# Validation.net
KiCad netlist of a schematic drawn in EAGLE
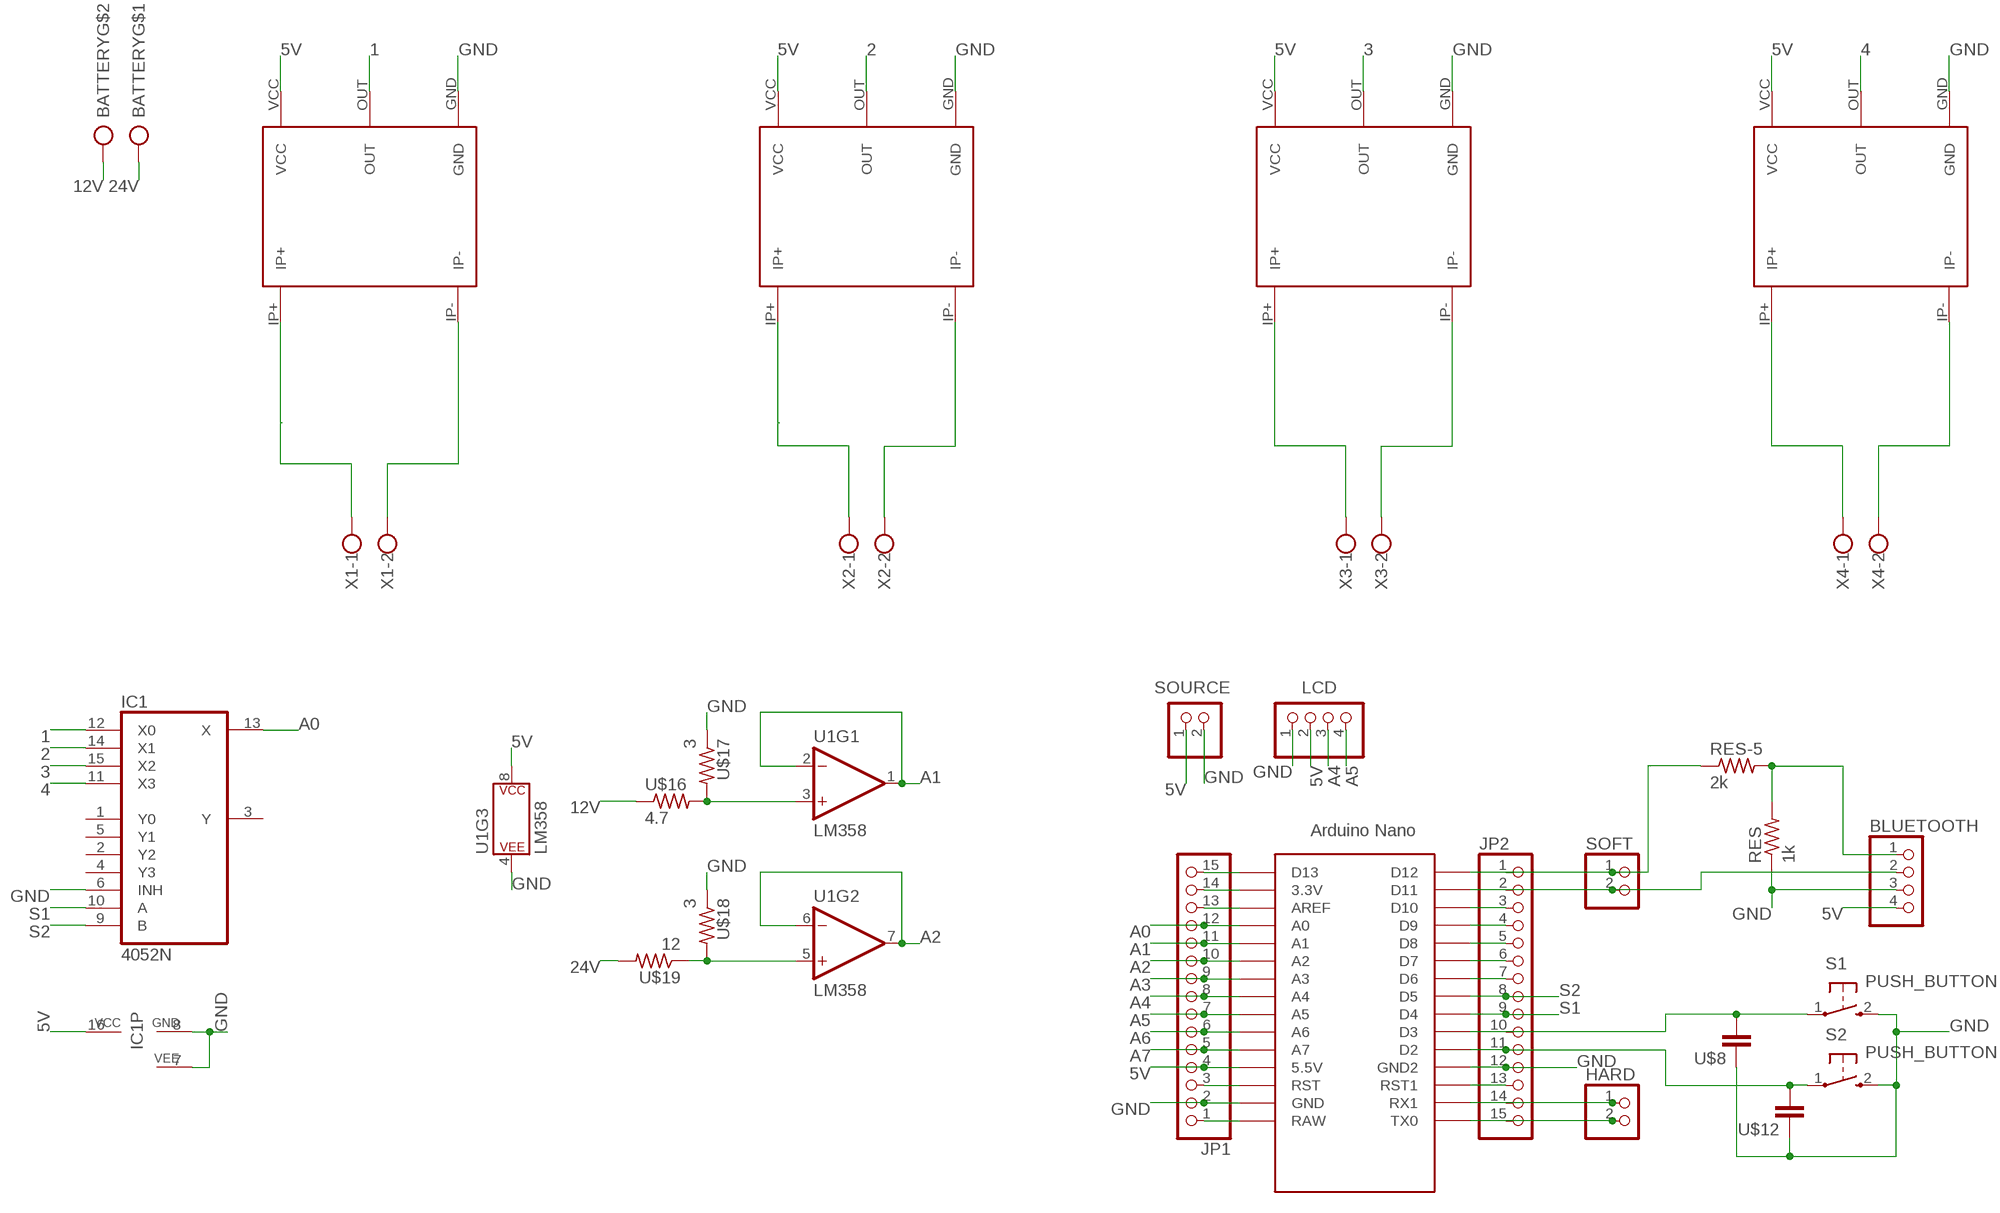
[diagram p0: schematic, sheet 1]

(export (version "E")
  (design (tool "Eeschema 10.0.6"))
  (components
    (comp (ref "BATTERY")
      (value "CON_PTR_2")
      (footprint "eagle-import:AK300_2")
      (libsource (lib "eagle-import") (part "CON_PTR_2"))
    )
    (comp (ref "BLUETOOTH")
      (value "PINHD-4_DATA")
      (footprint "eagle-import:1X04_DATA")
      (libsource (lib "eagle-import") (part "PINHD-4_DATA"))
    )
    (comp (ref "HARD")
      (value "PINHD-2_DATA")
      (footprint "eagle-import:1X02_DATA")
      (libsource (lib "eagle-import") (part "PINHD-2_DATA"))
    )
    (comp (ref "IC1")
      (value "4052N")
      (footprint "eagle-import:DIL16")
      (libsource (lib "eagle-import") (part "4052N"))
    )
    (comp (ref "JP1")
      (value "PINHD-1X15")
      (footprint "eagle-import:1X15")
      (libsource (lib "eagle-import") (part "PINHD-1X15"))
    )
    (comp (ref "JP2")
      (value "PINHD-1X15")
      (footprint "eagle-import:1X15")
      (libsource (lib "eagle-import") (part "PINHD-1X15"))
    )
    (comp (ref "LCD")
      (value "PINHD-4_DATA")
      (footprint "eagle-import:1X04_DATA")
      (libsource (lib "eagle-import") (part "PINHD-4_DATA"))
    )
    (comp (ref "RES")
      (value "1k")
      (footprint "eagle-import:0204_5")
      (libsource (lib "eagle-import") (part "RES-5"))
    )
    (comp (ref "RES-5")
      (value "2k")
      (footprint "eagle-import:0204_5")
      (libsource (lib "eagle-import") (part "RES-5"))
    )
    (comp (ref "S1")
      (value "PUSH_BUTTON")
      (footprint "eagle-import:B3F-10XX")
      (libsource (lib "eagle-import") (part "PUSH_BUTTON"))
    )
    (comp (ref "S2")
      (value "PUSH_BUTTON")
      (footprint "eagle-import:B3F-10XX")
      (libsource (lib "eagle-import") (part "PUSH_BUTTON"))
    )
    (comp (ref "SOFT")
      (value "PINHD-2_DATA")
      (footprint "eagle-import:1X02_DATA")
      (libsource (lib "eagle-import") (part "PINHD-2_DATA"))
    )
    (comp (ref "SOURCE")
      (value "PINHD-2_DATA")
      (footprint "eagle-import:1X02_DATA")
      (libsource (lib "eagle-import") (part "PINHD-2_DATA"))
    )
    (comp (ref "U$1")
      (value "ASC712_MODULE")
      (footprint "eagle-import:ASC712_MODULE")
      (libsource (lib "eagle-import") (part "ASC712_MODULE"))
    )
    (comp (ref "U$4")
      (value "ARDUINO_NANO")
      (footprint "eagle-import:NANO")
      (libsource (lib "eagle-import") (part "ARDUINO_NANO"))
    )
    (comp (ref "U$5")
      (value "ASC712_MODULE")
      (footprint "eagle-import:ASC712_MODULE")
      (libsource (lib "eagle-import") (part "ASC712_MODULE"))
    )
    (comp (ref "U$8")
      (value "CAPACITOR")
      (footprint "eagle-import:C025-025X050")
      (libsource (lib "eagle-import") (part "CAPACITOR"))
    )
    (comp (ref "U$9")
      (value "ASC712_MODULE")
      (footprint "eagle-import:ASC712_MODULE")
      (libsource (lib "eagle-import") (part "ASC712_MODULE"))
    )
    (comp (ref "U$12")
      (value "CAPACITOR")
      (footprint "eagle-import:C025-025X050")
      (libsource (lib "eagle-import") (part "CAPACITOR"))
    )
    (comp (ref "U$13")
      (value "ASC712_MODULE")
      (footprint "eagle-import:ASC712_MODULE")
      (libsource (lib "eagle-import") (part "ASC712_MODULE"))
    )
    (comp (ref "U$16")
      (value "4.7")
      (footprint "eagle-import:0204_7")
      (libsource (lib "eagle-import") (part "RES-7"))
    )
    (comp (ref "U$17")
      (value "3")
      (footprint "eagle-import:0204_7")
      (libsource (lib "eagle-import") (part "RES-7"))
    )
    (comp (ref "U$18")
      (value "3")
      (footprint "eagle-import:0204_7")
      (libsource (lib "eagle-import") (part "RES-7"))
    )
    (comp (ref "U$19")
      (value "12")
      (footprint "eagle-import:0204_7")
      (libsource (lib "eagle-import") (part "RES-7"))
    )
    (comp (ref "U1")
      (value "LM358")
      (footprint "eagle-import:DIP08")
      (libsource (lib "eagle-import") (part "LM358"))
    )
    (comp (ref "X1")
      (value "ROSTA.POWER")
      (footprint "eagle-import:W239-302")
      (libsource (lib "eagle-import") (part "ROSTA.POWER"))
    )
    (comp (ref "X2")
      (value "ROSTA.POWER")
      (footprint "eagle-import:W239-302")
      (libsource (lib "eagle-import") (part "ROSTA.POWER"))
    )
    (comp (ref "X3")
      (value "ROSTA.POWER")
      (footprint "eagle-import:W239-302")
      (libsource (lib "eagle-import") (part "ROSTA.POWER"))
    )
    (comp (ref "X4")
      (value "ROSTA.POWER")
      (footprint "eagle-import:W239-302")
      (libsource (lib "eagle-import") (part "ROSTA.POWER"))
    )
  )
  (nets
    (net (code "1") (name "/1") (class "Default")
      (node (ref "IC1") (pin "12") (pinfunction "X0_12") (pintype "bidirectional"))
      (node (ref "U$1") (pin "OUT") (pinfunction "OUT_OUT") (pintype "bidirectional"))
    )
    (net (code "2") (name "/2") (class "Default")
      (node (ref "IC1") (pin "14") (pinfunction "X1_14") (pintype "bidirectional"))
      (node (ref "U$5") (pin "OUT") (pinfunction "OUT_OUT") (pintype "bidirectional"))
    )
    (net (code "3") (name "/3") (class "Default")
      (node (ref "IC1") (pin "15") (pinfunction "X2_15") (pintype "bidirectional"))
      (node (ref "U$9") (pin "OUT") (pinfunction "OUT_OUT") (pintype "bidirectional"))
    )
    (net (code "4") (name "/4") (class "Default")
      (node (ref "IC1") (pin "11") (pinfunction "X3_11") (pintype "bidirectional"))
      (node (ref "U$13") (pin "OUT") (pinfunction "OUT_OUT") (pintype "bidirectional"))
    )
    (net (code "5") (name "/5V") (class "Default")
      (node (ref "BLUETOOTH") (pin "4") (pinfunction "4_4") (pintype "passive"))
      (node (ref "IC1") (pin "16") (pinfunction "VCC_16") (pintype "power_in"))
      (node (ref "JP1") (pin "4") (pinfunction "4_4") (pintype "passive"))
      (node (ref "LCD") (pin "2") (pinfunction "2_2") (pintype "passive"))
      (node (ref "SOURCE") (pin "1") (pinfunction "1_1") (pintype "passive"))
      (node (ref "U$1") (pin "VCC") (pinfunction "VCC_VCC") (pintype "bidirectional"))
      (node (ref "U$13") (pin "VCC") (pinfunction "VCC_VCC") (pintype "bidirectional"))
      (node (ref "U$4") (pin "5V") (pinfunction "5.5V_5V") (pintype "bidirectional"))
      (node (ref "U$5") (pin "VCC") (pinfunction "VCC_VCC") (pintype "bidirectional"))
      (node (ref "U$9") (pin "VCC") (pinfunction "VCC_VCC") (pintype "bidirectional"))
      (node (ref "U1") (pin "8") (pinfunction "P$V+_8") (pintype "bidirectional"))
    )
    (net (code "6") (name "/12V") (class "Default")
      (node (ref "BATTERY") (pin "2") (pinfunction "KL_2") (pintype "passive"))
      (node (ref "U$16") (pin "1") (pinfunction "1_1") (pintype "passive"))
    )
    (net (code "7") (name "/24V") (class "Default")
      (node (ref "BATTERY") (pin "1") (pinfunction "KL_1") (pintype "passive"))
      (node (ref "U$19") (pin "2") (pinfunction "2_2") (pintype "passive"))
    )
    (net (code "8") (name "/A0") (class "Default")
      (node (ref "IC1") (pin "13") (pinfunction "X_13") (pintype "bidirectional"))
      (node (ref "JP1") (pin "12") (pinfunction "12_12") (pintype "passive"))
      (node (ref "U$4") (pin "A0") (pinfunction "A0_A0") (pintype "bidirectional"))
    )
    (net (code "9") (name "/A1") (class "Default")
      (node (ref "JP1") (pin "11") (pinfunction "11_11") (pintype "passive"))
      (node (ref "U$4") (pin "A1") (pinfunction "A1_A1") (pintype "bidirectional"))
      (node (ref "U1") (pin "1") (pinfunction "OUT_1") (pintype "output"))
      (node (ref "U1") (pin "2") (pinfunction "-IN_2") (pintype "input"))
    )
    (net (code "10") (name "/A2") (class "Default")
      (node (ref "JP1") (pin "10") (pinfunction "10_10") (pintype "passive"))
      (node (ref "U$4") (pin "A2") (pinfunction "A2_A2") (pintype "bidirectional"))
      (node (ref "U1") (pin "6") (pinfunction "-IN_6") (pintype "input"))
      (node (ref "U1") (pin "7") (pinfunction "OUT_7") (pintype "output"))
    )
    (net (code "11") (name "/A3") (class "Default")
      (node (ref "JP1") (pin "9") (pinfunction "9_9") (pintype "passive"))
      (node (ref "U$4") (pin "A3") (pinfunction "A3_A3") (pintype "bidirectional"))
    )
    (net (code "12") (name "/A4") (class "Default")
      (node (ref "JP1") (pin "8") (pinfunction "8_8") (pintype "passive"))
      (node (ref "LCD") (pin "3") (pinfunction "3_3") (pintype "passive"))
      (node (ref "U$4") (pin "A4") (pinfunction "A4_A4") (pintype "bidirectional"))
    )
    (net (code "13") (name "/A5") (class "Default")
      (node (ref "JP1") (pin "7") (pinfunction "7_7") (pintype "passive"))
      (node (ref "LCD") (pin "4") (pinfunction "4_4") (pintype "passive"))
      (node (ref "U$4") (pin "A5") (pinfunction "A5_A5") (pintype "bidirectional"))
    )
    (net (code "14") (name "/A6") (class "Default")
      (node (ref "JP1") (pin "6") (pinfunction "6_6") (pintype "passive"))
      (node (ref "U$4") (pin "A6") (pinfunction "A6_A6") (pintype "bidirectional"))
    )
    (net (code "15") (name "/A7") (class "Default")
      (node (ref "JP1") (pin "5") (pinfunction "5_5") (pintype "passive"))
      (node (ref "U$4") (pin "A7") (pinfunction "A7_A7") (pintype "bidirectional"))
    )
    (net (code "16") (name "/GND") (class "Default")
      (node (ref "BLUETOOTH") (pin "3") (pinfunction "3_3") (pintype "passive"))
      (node (ref "IC1") (pin "6") (pinfunction "INH_6") (pintype "input"))
      (node (ref "IC1") (pin "7") (pinfunction "VEE_7") (pintype "power_in"))
      (node (ref "IC1") (pin "8") (pinfunction "GND_8") (pintype "power_in"))
      (node (ref "JP1") (pin "2") (pinfunction "2_2") (pintype "passive"))
      (node (ref "JP2") (pin "12") (pinfunction "12_12") (pintype "passive"))
      (node (ref "LCD") (pin "1") (pinfunction "1_1") (pintype "passive"))
      (node (ref "RES") (pin "1") (pinfunction "1_1") (pintype "passive"))
      (node (ref "S1") (pin "2") (pinfunction "S_2") (pintype "passive"))
      (node (ref "S2") (pin "2") (pinfunction "S_2") (pintype "passive"))
      (node (ref "SOURCE") (pin "2") (pinfunction "2_2") (pintype "passive"))
      (node (ref "U$1") (pin "GND") (pinfunction "GND_GND") (pintype "bidirectional"))
      (node (ref "U$12") (pin "1") (pinfunction "1_1") (pintype "passive"))
      (node (ref "U$13") (pin "GND") (pinfunction "GND_GND") (pintype "bidirectional"))
      (node (ref "U$17") (pin "1") (pinfunction "1_1") (pintype "passive"))
      (node (ref "U$18") (pin "1") (pinfunction "1_1") (pintype "passive"))
      (node (ref "U$4") (pin "GND") (pinfunction "GND_GND") (pintype "bidirectional"))
      (node (ref "U$4") (pin "GND1") (pinfunction "GND2_GND1") (pintype "bidirectional"))
      (node (ref "U$5") (pin "GND") (pinfunction "GND_GND") (pintype "bidirectional"))
      (node (ref "U$8") (pin "1") (pinfunction "1_1") (pintype "passive"))
      (node (ref "U$9") (pin "GND") (pinfunction "GND_GND") (pintype "bidirectional"))
      (node (ref "U1") (pin "4") (pinfunction "P$V-_4") (pintype "bidirectional"))
    )
    (net (code "17") (name "/S1") (class "Default")
      (node (ref "IC1") (pin "10") (pinfunction "A_10") (pintype "input"))
      (node (ref "JP2") (pin "9") (pinfunction "9_9") (pintype "passive"))
      (node (ref "U$4") (pin "D4") (pinfunction "D4_D4") (pintype "bidirectional"))
    )
    (net (code "18") (name "/S2") (class "Default")
      (node (ref "IC1") (pin "9") (pinfunction "B_9") (pintype "input"))
      (node (ref "JP2") (pin "8") (pinfunction "8_8") (pintype "passive"))
      (node (ref "U$4") (pin "D5") (pinfunction "D5_D5") (pintype "bidirectional"))
    )
    (net (code "19") (name "Net-(BLUETOOTH-Pad1)") (class "Default")
      (node (ref "BLUETOOTH") (pin "1") (pinfunction "1_1") (pintype "passive"))
      (node (ref "RES") (pin "2") (pinfunction "2_2") (pintype "passive"))
      (node (ref "RES-5") (pin "2") (pinfunction "2_2") (pintype "passive"))
    )
    (net (code "20") (name "Net-(BLUETOOTH-Pad2)") (class "Default")
      (node (ref "BLUETOOTH") (pin "2") (pinfunction "2_2") (pintype "passive"))
      (node (ref "JP2") (pin "2") (pinfunction "2_2") (pintype "passive"))
      (node (ref "SOFT") (pin "2") (pinfunction "2_2") (pintype "passive"))
      (node (ref "U$4") (pin "D11") (pinfunction "D11_D11") (pintype "bidirectional"))
    )
    (net (code "21") (name "Net-(HARD-Pad1)") (class "Default")
      (node (ref "HARD") (pin "1") (pinfunction "1_1") (pintype "passive"))
      (node (ref "JP2") (pin "14") (pinfunction "14_14") (pintype "passive"))
      (node (ref "U$4") (pin "RX1") (pinfunction "RX1_RX1") (pintype "bidirectional"))
    )
    (net (code "22") (name "Net-(HARD-Pad2)") (class "Default")
      (node (ref "HARD") (pin "2") (pinfunction "2_2") (pintype "passive"))
      (node (ref "JP2") (pin "15") (pinfunction "15_15") (pintype "passive"))
      (node (ref "U$4") (pin "TX0") (pinfunction "TX0_TX0") (pintype "bidirectional"))
    )
    (net (code "23") (name "Net-(JP1-Pad1)") (class "Default")
      (node (ref "JP1") (pin "1") (pinfunction "1_1") (pintype "passive"))
      (node (ref "U$4") (pin "RAW") (pinfunction "RAW_RAW") (pintype "bidirectional"))
    )
    (net (code "24") (name "Net-(JP1-Pad3)") (class "Default")
      (node (ref "JP1") (pin "3") (pinfunction "3_3") (pintype "passive"))
      (node (ref "U$4") (pin "RST") (pinfunction "RST_RST") (pintype "bidirectional"))
    )
    (net (code "25") (name "Net-(JP1-Pad13)") (class "Default")
      (node (ref "JP1") (pin "13") (pinfunction "13_13") (pintype "passive"))
      (node (ref "U$4") (pin "AREF") (pinfunction "AREF_AREF") (pintype "bidirectional"))
    )
    (net (code "26") (name "Net-(JP1-Pad14)") (class "Default")
      (node (ref "JP1") (pin "14") (pinfunction "14_14") (pintype "passive"))
      (node (ref "U$4") (pin "3.3V") (pinfunction "3.3V_3.3V") (pintype "bidirectional"))
    )
    (net (code "27") (name "Net-(JP1-Pad15)") (class "Default")
      (node (ref "JP1") (pin "15") (pinfunction "15_15") (pintype "passive"))
      (node (ref "U$4") (pin "D13") (pinfunction "D13_D13") (pintype "bidirectional"))
    )
    (net (code "28") (name "Net-(JP2-Pad1)") (class "Default")
      (node (ref "JP2") (pin "1") (pinfunction "1_1") (pintype "passive"))
      (node (ref "RES-5") (pin "1") (pinfunction "1_1") (pintype "passive"))
      (node (ref "SOFT") (pin "1") (pinfunction "1_1") (pintype "passive"))
      (node (ref "U$4") (pin "D12") (pinfunction "D12_D12") (pintype "bidirectional"))
    )
    (net (code "29") (name "Net-(JP2-Pad3)") (class "Default")
      (node (ref "JP2") (pin "3") (pinfunction "3_3") (pintype "passive"))
      (node (ref "U$4") (pin "D10") (pinfunction "D10_D10") (pintype "bidirectional"))
    )
    (net (code "30") (name "Net-(JP2-Pad4)") (class "Default")
      (node (ref "JP2") (pin "4") (pinfunction "4_4") (pintype "passive"))
      (node (ref "U$4") (pin "D9") (pinfunction "D9_D9") (pintype "bidirectional"))
    )
    (net (code "31") (name "Net-(JP2-Pad5)") (class "Default")
      (node (ref "JP2") (pin "5") (pinfunction "5_5") (pintype "passive"))
      (node (ref "U$4") (pin "D8") (pinfunction "D8_D8") (pintype "bidirectional"))
    )
    (net (code "32") (name "Net-(JP2-Pad6)") (class "Default")
      (node (ref "JP2") (pin "6") (pinfunction "6_6") (pintype "passive"))
      (node (ref "U$4") (pin "D7") (pinfunction "D7_D7") (pintype "bidirectional"))
    )
    (net (code "33") (name "Net-(JP2-Pad7)") (class "Default")
      (node (ref "JP2") (pin "7") (pinfunction "7_7") (pintype "passive"))
      (node (ref "U$4") (pin "D6") (pinfunction "D6_D6") (pintype "bidirectional"))
    )
    (net (code "34") (name "Net-(JP2-Pad13)") (class "Default")
      (node (ref "JP2") (pin "13") (pinfunction "13_13") (pintype "passive"))
      (node (ref "U$4") (pin "RST1") (pinfunction "RST1_RST1") (pintype "bidirectional"))
    )
    (net (code "35") (name "Net-(S1-P)") (class "Default")
      (node (ref "JP2") (pin "10") (pinfunction "10_10") (pintype "passive"))
      (node (ref "S1") (pin "1") (pinfunction "P_1") (pintype "passive"))
      (node (ref "U$4") (pin "D3") (pinfunction "D3_D3") (pintype "bidirectional"))
      (node (ref "U$8") (pin "2") (pinfunction "2_2") (pintype "passive"))
    )
    (net (code "36") (name "Net-(S2-P)") (class "Default")
      (node (ref "JP2") (pin "11") (pinfunction "11_11") (pintype "passive"))
      (node (ref "S2") (pin "1") (pinfunction "P_1") (pintype "passive"))
      (node (ref "U$12") (pin "2") (pinfunction "2_2") (pintype "passive"))
      (node (ref "U$4") (pin "D2") (pinfunction "D2_D2") (pintype "bidirectional"))
    )
    (net (code "37") (name "Net-(U1A-+IN)") (class "Default")
      (node (ref "U$16") (pin "2") (pinfunction "2_2") (pintype "passive"))
      (node (ref "U$17") (pin "2") (pinfunction "2_2") (pintype "passive"))
      (node (ref "U1") (pin "3") (pinfunction "+IN_3") (pintype "input"))
    )
    (net (code "38") (name "Net-(U1B-+IN)") (class "Default")
      (node (ref "U$18") (pin "2") (pinfunction "2_2") (pintype "passive"))
      (node (ref "U$19") (pin "1") (pinfunction "1_1") (pintype "passive"))
      (node (ref "U1") (pin "5") (pinfunction "+IN_5") (pintype "input"))
    )
    (net (code "39") (name "Net-(X1A-KL)") (class "Default")
      (node (ref "U$1") (pin "IP+") (pinfunction "IP+_IP+") (pintype "bidirectional"))
      (node (ref "X1") (pin "1") (pinfunction "KL_1") (pintype "passive"))
    )
    (net (code "40") (name "Net-(X1B-KL)") (class "Default")
      (node (ref "U$1") (pin "IP-") (pinfunction "IP-_IP-") (pintype "bidirectional"))
      (node (ref "X1") (pin "2") (pinfunction "KL_2") (pintype "passive"))
    )
    (net (code "41") (name "Net-(X2A-KL)") (class "Default")
      (node (ref "U$5") (pin "IP+") (pinfunction "IP+_IP+") (pintype "bidirectional"))
      (node (ref "X2") (pin "1") (pinfunction "KL_1") (pintype "passive"))
    )
    (net (code "42") (name "Net-(X2B-KL)") (class "Default")
      (node (ref "U$5") (pin "IP-") (pinfunction "IP-_IP-") (pintype "bidirectional"))
      (node (ref "X2") (pin "2") (pinfunction "KL_2") (pintype "passive"))
    )
    (net (code "43") (name "Net-(X3A-KL)") (class "Default")
      (node (ref "U$9") (pin "IP+") (pinfunction "IP+_IP+") (pintype "bidirectional"))
      (node (ref "X3") (pin "1") (pinfunction "KL_1") (pintype "passive"))
    )
    (net (code "44") (name "Net-(X3B-KL)") (class "Default")
      (node (ref "U$9") (pin "IP-") (pinfunction "IP-_IP-") (pintype "bidirectional"))
      (node (ref "X3") (pin "2") (pinfunction "KL_2") (pintype "passive"))
    )
    (net (code "45") (name "Net-(X4A-KL)") (class "Default")
      (node (ref "U$13") (pin "IP+") (pinfunction "IP+_IP+") (pintype "bidirectional"))
      (node (ref "X4") (pin "1") (pinfunction "KL_1") (pintype "passive"))
    )
    (net (code "46") (name "Net-(X4B-KL)") (class "Default")
      (node (ref "U$13") (pin "IP-") (pinfunction "IP-_IP-") (pintype "bidirectional"))
      (node (ref "X4") (pin "2") (pinfunction "KL_2") (pintype "passive"))
    )
    (net (code "47") (name "unconnected-(IC1A-Y-Pad3)") (class "Default")
      (node (ref "IC1") (pin "3") (pinfunction "Y_3") (pintype "bidirectional"))
    )
    (net (code "48") (name "unconnected-(IC1A-Y0-Pad1)") (class "Default")
      (node (ref "IC1") (pin "1") (pinfunction "Y0_1") (pintype "bidirectional"))
    )
    (net (code "49") (name "unconnected-(IC1A-Y1-Pad5)") (class "Default")
      (node (ref "IC1") (pin "5") (pinfunction "Y1_5") (pintype "bidirectional"))
    )
    (net (code "50") (name "unconnected-(IC1A-Y2-Pad2)") (class "Default")
      (node (ref "IC1") (pin "2") (pinfunction "Y2_2") (pintype "bidirectional"))
    )
    (net (code "51") (name "unconnected-(IC1A-Y3-Pad4)") (class "Default")
      (node (ref "IC1") (pin "4") (pinfunction "Y3_4") (pintype "bidirectional"))
    )
  )
)
